# system.net
KiCad netlist of a schematic drawn in EAGLE
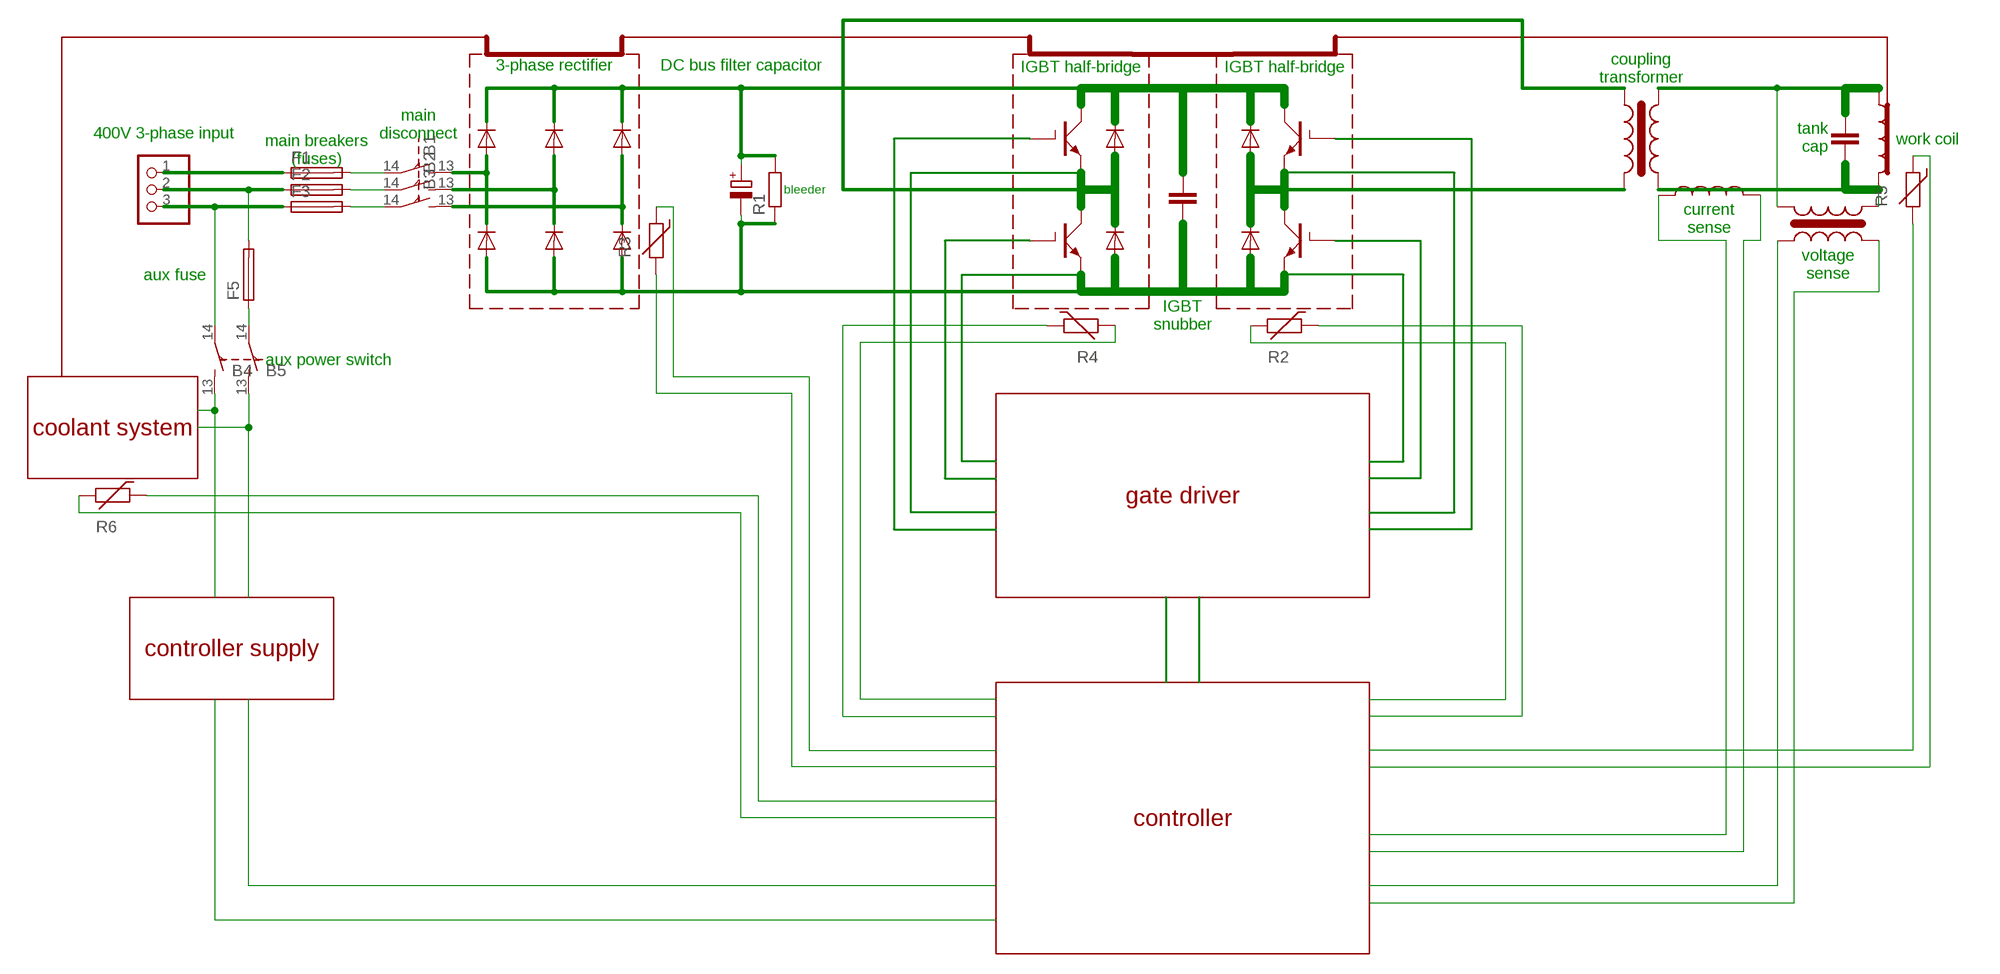
[diagram p0: schematic, sheet 1]

(export (version "E")
  (design (tool "Eeschema 10.0.6"))
  (components
    (comp (ref "B1")
      (value "ENDSCHALTER_SCHLIESSER")
      (footprint "eagle-import:ENDSCHALTER_SCHLIESSER")
      (libsource (lib "eagle-import") (part "ENDSCHALTER_SCHLIESSER"))
    )
    (comp (ref "B2")
      (value "ENDSCHALTER_SCHLIESSER")
      (footprint "eagle-import:ENDSCHALTER_SCHLIESSER")
      (libsource (lib "eagle-import") (part "ENDSCHALTER_SCHLIESSER"))
    )
    (comp (ref "B3")
      (value "ENDSCHALTER_SCHLIESSER")
      (footprint "eagle-import:ENDSCHALTER_SCHLIESSER")
      (libsource (lib "eagle-import") (part "ENDSCHALTER_SCHLIESSER"))
    )
    (comp (ref "B4")
      (value "ENDSCHALTER_SCHLIESSER")
      (footprint "eagle-import:ENDSCHALTER_SCHLIESSER")
      (libsource (lib "eagle-import") (part "ENDSCHALTER_SCHLIESSER"))
    )
    (comp (ref "B5")
      (value "ENDSCHALTER_SCHLIESSER")
      (footprint "eagle-import:ENDSCHALTER_SCHLIESSER")
      (libsource (lib "eagle-import") (part "ENDSCHALTER_SCHLIESSER"))
    )
    (comp (ref "C1")
      (value "CPOL-EU085CS-1AR")
      (footprint "eagle-import:085CS_1AR")
      (libsource (lib "eagle-import") (part "CPOL-EU085CS-1AR"))
    )
    (comp (ref "C2")
      (value "C-EU025-024X044")
      (footprint "eagle-import:C025-024X044")
      (libsource (lib "eagle-import") (part "C-EU025-024X044"))
    )
    (comp (ref "C3")
      (value "C-EU025-024X044")
      (footprint "eagle-import:C025-024X044")
      (libsource (lib "eagle-import") (part "C-EU025-024X044"))
    )
    (comp (ref "D1")
      (value "1N4004")
      (footprint "eagle-import:DO41-10")
      (libsource (lib "eagle-import") (part "1N4004"))
    )
    (comp (ref "D2")
      (value "1N4004")
      (footprint "eagle-import:DO41-10")
      (libsource (lib "eagle-import") (part "1N4004"))
    )
    (comp (ref "D3")
      (value "1N4004")
      (footprint "eagle-import:DO41-10")
      (libsource (lib "eagle-import") (part "1N4004"))
    )
    (comp (ref "D4")
      (value "1N4004")
      (footprint "eagle-import:DO41-10")
      (libsource (lib "eagle-import") (part "1N4004"))
    )
    (comp (ref "D5")
      (value "1N4004")
      (footprint "eagle-import:DO41-10")
      (libsource (lib "eagle-import") (part "1N4004"))
    )
    (comp (ref "D6")
      (value "1N4004")
      (footprint "eagle-import:DO41-10")
      (libsource (lib "eagle-import") (part "1N4004"))
    )
    (comp (ref "D7")
      (value "1N4004")
      (footprint "eagle-import:DO41-10")
      (libsource (lib "eagle-import") (part "1N4004"))
    )
    (comp (ref "D8")
      (value "1N4004")
      (footprint "eagle-import:DO41-10")
      (libsource (lib "eagle-import") (part "1N4004"))
    )
    (comp (ref "D9")
      (value "1N4004")
      (footprint "eagle-import:DO41-10")
      (libsource (lib "eagle-import") (part "1N4004"))
    )
    (comp (ref "D10")
      (value "1N4004")
      (footprint "eagle-import:DO41-10")
      (libsource (lib "eagle-import") (part "1N4004"))
    )
    (comp (ref "F1")
      (value "GSH15")
      (footprint "eagle-import:GSH15")
      (fields (field (name "MPN") "64900001039"))
      (libsource (lib "eagle-import") (part "GSH15"))
    )
    (comp (ref "F2")
      (value "GSH15")
      (footprint "eagle-import:GSH15")
      (fields (field (name "MPN") "64900001039"))
      (libsource (lib "eagle-import") (part "GSH15"))
    )
    (comp (ref "F3")
      (value "GSH15")
      (footprint "eagle-import:GSH15")
      (fields (field (name "MPN") "64900001039"))
      (libsource (lib "eagle-import") (part "GSH15"))
    )
    (comp (ref "F5")
      (value "GSH15")
      (footprint "eagle-import:GSH15")
      (fields (field (name "MPN") "64900001039"))
      (libsource (lib "eagle-import") (part "GSH15"))
    )
    (comp (ref "JP1")
      (value "PINHD-1X3")
      (footprint "eagle-import:1X03")
      (libsource (lib "eagle-import") (part "PINHD-1X3"))
    )
    (comp (ref "L1")
      (value "L-US0204/5")
      (footprint "eagle-import:0204_5")
      (libsource (lib "eagle-import") (part "L-US0204/5"))
    )
    (comp (ref "L12")
      (value "L-US0204/5")
      (footprint "eagle-import:0204_5")
      (libsource (lib "eagle-import") (part "L-US0204/5"))
    )
    (comp (ref "L13")
      (value "L-US0204/5")
      (footprint "eagle-import:0204_5")
      (libsource (lib "eagle-import") (part "L-US0204/5"))
    )
    (comp (ref "L14")
      (value "L-US0204/5")
      (footprint "eagle-import:0204_5")
      (libsource (lib "eagle-import") (part "L-US0204/5"))
    )
    (comp (ref "L15")
      (value "L-US0204/5")
      (footprint "eagle-import:0204_5")
      (libsource (lib "eagle-import") (part "L-US0204/5"))
    )
    (comp (ref "L16")
      (value "L-US0204/5")
      (footprint "eagle-import:0204_5")
      (libsource (lib "eagle-import") (part "L-US0204/5"))
    )
    (comp (ref "Q1")
      (value "IXGT6N170")
      (footprint "eagle-import:TO268")
      (libsource (lib "eagle-import") (part "IXG?N170T6"))
    )
    (comp (ref "Q2")
      (value "IXGT6N170")
      (footprint "eagle-import:TO268")
      (libsource (lib "eagle-import") (part "IXG?N170T6"))
    )
    (comp (ref "Q3")
      (value "IXGT6N170")
      (footprint "eagle-import:TO268")
      (libsource (lib "eagle-import") (part "IXG?N170T6"))
    )
    (comp (ref "Q4")
      (value "IXGT6N170")
      (footprint "eagle-import:TO268")
      (libsource (lib "eagle-import") (part "IXG?N170T6"))
    )
    (comp (ref "R1")
      (value "R-EU_0204/2V")
      (footprint "eagle-import:0204V")
      (libsource (lib "eagle-import") (part "R-EU_0204/2V"))
    )
    (comp (ref "R2")
      (value "THERMISTOR-2,5")
      (footprint "eagle-import:RS-2,5")
      (libsource (lib "eagle-import") (part "THERMISTOR-2,5"))
    )
    (comp (ref "R3")
      (value "THERMISTOR-2,5")
      (footprint "eagle-import:RS-2,5")
      (libsource (lib "eagle-import") (part "THERMISTOR-2,5"))
    )
    (comp (ref "R4")
      (value "THERMISTOR-2,5")
      (footprint "eagle-import:RS-2,5")
      (libsource (lib "eagle-import") (part "THERMISTOR-2,5"))
    )
    (comp (ref "R5")
      (value "THERMISTOR-2,5")
      (footprint "eagle-import:RS-2,5")
      (libsource (lib "eagle-import") (part "THERMISTOR-2,5"))
    )
    (comp (ref "R6")
      (value "THERMISTOR-2,5")
      (footprint "eagle-import:RS-2,5")
      (libsource (lib "eagle-import") (part "THERMISTOR-2,5"))
    )
  )
  (nets
    (net (code "1") (name "Net-(B1-3)") (class "Default")
      (node (ref "B1") (pin "13") (pinfunction "3_13") (pintype "passive"))
      (node (ref "D2") (pin "A") (pinfunction "A_A") (pintype "passive"))
      (node (ref "D3") (pin "C") (pinfunction "C_C") (pintype "passive"))
    )
    (net (code "2") (name "Net-(B1-4)") (class "Default")
      (node (ref "B1") (pin "14") (pinfunction "4_14") (pintype "passive"))
      (node (ref "F1") (pin "2") (pinfunction "2_2") (pintype "passive"))
    )
    (net (code "3") (name "Net-(B2-3)") (class "Default")
      (node (ref "B2") (pin "13") (pinfunction "3_13") (pintype "passive"))
      (node (ref "D4") (pin "A") (pinfunction "A_A") (pintype "passive"))
      (node (ref "D5") (pin "C") (pinfunction "C_C") (pintype "passive"))
    )
    (net (code "4") (name "Net-(B2-4)") (class "Default")
      (node (ref "B2") (pin "14") (pinfunction "4_14") (pintype "passive"))
      (node (ref "F2") (pin "2") (pinfunction "2_2") (pintype "passive"))
    )
    (net (code "5") (name "Net-(B3-3)") (class "Default")
      (node (ref "B3") (pin "13") (pinfunction "3_13") (pintype "passive"))
      (node (ref "D6") (pin "A") (pinfunction "A_A") (pintype "passive"))
      (node (ref "D7") (pin "C") (pinfunction "C_C") (pintype "passive"))
    )
    (net (code "6") (name "Net-(B3-4)") (class "Default")
      (node (ref "B3") (pin "14") (pinfunction "4_14") (pintype "passive"))
      (node (ref "F3") (pin "2") (pinfunction "2_2") (pintype "passive"))
    )
    (net (code "7") (name "Net-(B4-4)") (class "Default")
      (node (ref "B4") (pin "14") (pinfunction "4_14") (pintype "passive"))
      (node (ref "F3") (pin "1") (pinfunction "1_1") (pintype "passive"))
      (node (ref "JP1") (pin "3") (pinfunction "3_3") (pintype "passive"))
    )
    (net (code "8") (name "Net-(B5-4)") (class "Default")
      (node (ref "B5") (pin "14") (pinfunction "4_14") (pintype "passive"))
      (node (ref "F5") (pin "1") (pinfunction "1_1") (pintype "passive"))
    )
    (net (code "9") (name "Net-(C1-Pad+)") (class "Default")
      (node (ref "C1") (pin "+") (pinfunction "+_+") (pintype "passive"))
      (node (ref "C3") (pin "1") (pinfunction "1_1") (pintype "passive"))
      (node (ref "D10") (pin "C") (pinfunction "C_C") (pintype "passive"))
      (node (ref "D2") (pin "C") (pinfunction "C_C") (pintype "passive"))
      (node (ref "D4") (pin "C") (pinfunction "C_C") (pintype "passive"))
      (node (ref "D6") (pin "C") (pinfunction "C_C") (pintype "passive"))
      (node (ref "D8") (pin "C") (pinfunction "C_C") (pintype "passive"))
      (node (ref "Q2") (pin "C@1") (pinfunction "C_C@1") (pintype "passive"))
      (node (ref "Q2") (pin "C@2") (pinfunction "C_C@2") (pintype "passive"))
      (node (ref "Q4") (pin "C@1") (pinfunction "C_C@1") (pintype "passive"))
      (node (ref "Q4") (pin "C@2") (pinfunction "C_C@2") (pintype "passive"))
      (node (ref "R1") (pin "2") (pinfunction "2_2") (pintype "passive"))
    )
    (net (code "10") (name "Net-(C1-Pad-)") (class "Default")
      (node (ref "C1") (pin "-") (pinfunction "-_-") (pintype "passive"))
      (node (ref "C3") (pin "2") (pinfunction "2_2") (pintype "passive"))
      (node (ref "D1") (pin "A") (pinfunction "A_A") (pintype "passive"))
      (node (ref "D3") (pin "A") (pinfunction "A_A") (pintype "passive"))
      (node (ref "D5") (pin "A") (pinfunction "A_A") (pintype "passive"))
      (node (ref "D7") (pin "A") (pinfunction "A_A") (pintype "passive"))
      (node (ref "D9") (pin "A") (pinfunction "A_A") (pintype "passive"))
      (node (ref "Q1") (pin "E") (pinfunction "E_E") (pintype "passive"))
      (node (ref "Q3") (pin "E") (pinfunction "E_E") (pintype "passive"))
      (node (ref "R1") (pin "1") (pinfunction "1_1") (pintype "passive"))
    )
    (net (code "11") (name "Net-(C2-Pad1)") (class "Default")
      (node (ref "C2") (pin "1") (pinfunction "1_1") (pintype "passive"))
      (node (ref "L1") (pin "1") (pinfunction "1_1") (pintype "passive"))
      (node (ref "L14") (pin "1") (pinfunction "1_1") (pintype "passive"))
      (node (ref "L15") (pin "2") (pinfunction "2_2") (pintype "passive"))
    )
    (net (code "12") (name "Net-(C2-Pad2)") (class "Default")
      (node (ref "C2") (pin "2") (pinfunction "2_2") (pintype "passive"))
      (node (ref "L1") (pin "2") (pinfunction "2_2") (pintype "passive"))
      (node (ref "L14") (pin "2") (pinfunction "2_2") (pintype "passive"))
      (node (ref "L15") (pin "1") (pinfunction "1_1") (pintype "passive"))
    )
    (net (code "13") (name "Net-(D1-PadC)") (class "Default")
      (node (ref "D1") (pin "C") (pinfunction "C_C") (pintype "passive"))
      (node (ref "D8") (pin "A") (pinfunction "A_A") (pintype "passive"))
      (node (ref "L13") (pin "1") (pinfunction "1_1") (pintype "passive"))
      (node (ref "Q1") (pin "C@1") (pinfunction "C_C@1") (pintype "passive"))
      (node (ref "Q1") (pin "C@2") (pinfunction "C_C@2") (pintype "passive"))
      (node (ref "Q2") (pin "E") (pinfunction "E_E") (pintype "passive"))
    )
    (net (code "14") (name "Net-(D10-PadA)") (class "Default")
      (node (ref "D10") (pin "A") (pinfunction "A_A") (pintype "passive"))
      (node (ref "D9") (pin "C") (pinfunction "C_C") (pintype "passive"))
      (node (ref "L13") (pin "2") (pinfunction "2_2") (pintype "passive"))
      (node (ref "Q3") (pin "C@1") (pinfunction "C_C@1") (pintype "passive"))
      (node (ref "Q3") (pin "C@2") (pinfunction "C_C@2") (pintype "passive"))
      (node (ref "Q4") (pin "E") (pinfunction "E_E") (pintype "passive"))
    )
    (net (code "15") (name "Net-(F1-Pad1)") (class "Default")
      (node (ref "F1") (pin "1") (pinfunction "1_1") (pintype "passive"))
      (node (ref "JP1") (pin "1") (pinfunction "1_1") (pintype "passive"))
    )
    (net (code "16") (name "Net-(F2-Pad1)") (class "Default")
      (node (ref "F2") (pin "1") (pinfunction "1_1") (pintype "passive"))
      (node (ref "F5") (pin "2") (pinfunction "2_2") (pintype "passive"))
      (node (ref "JP1") (pin "2") (pinfunction "2_2") (pintype "passive"))
    )
    (net (code "17") (name "unconnected-(B4-3-Pad13)") (class "Default")
      (node (ref "B4") (pin "13") (pinfunction "3_13") (pintype "passive"))
    )
    (net (code "18") (name "unconnected-(B5-3-Pad13)") (class "Default")
      (node (ref "B5") (pin "13") (pinfunction "3_13") (pintype "passive"))
    )
    (net (code "19") (name "unconnected-(L12-Pad1)") (class "Default")
      (node (ref "L12") (pin "1") (pinfunction "1_1") (pintype "passive"))
    )
    (net (code "20") (name "unconnected-(L12-Pad2)") (class "Default")
      (node (ref "L12") (pin "2") (pinfunction "2_2") (pintype "passive"))
    )
    (net (code "21") (name "unconnected-(L16-Pad1)") (class "Default")
      (node (ref "L16") (pin "1") (pinfunction "1_1") (pintype "passive"))
    )
    (net (code "22") (name "unconnected-(L16-Pad2)") (class "Default")
      (node (ref "L16") (pin "2") (pinfunction "2_2") (pintype "passive"))
    )
    (net (code "23") (name "unconnected-(Q1-PadG)") (class "Default")
      (node (ref "Q1") (pin "G") (pinfunction "G_G") (pintype "passive"))
    )
    (net (code "24") (name "unconnected-(Q2-PadG)") (class "Default")
      (node (ref "Q2") (pin "G") (pinfunction "G_G") (pintype "passive"))
    )
    (net (code "25") (name "unconnected-(Q3-PadG)") (class "Default")
      (node (ref "Q3") (pin "G") (pinfunction "G_G") (pintype "passive"))
    )
    (net (code "26") (name "unconnected-(Q4-PadG)") (class "Default")
      (node (ref "Q4") (pin "G") (pinfunction "G_G") (pintype "passive"))
    )
    (net (code "27") (name "unconnected-(R2-Pad1)") (class "Default")
      (node (ref "R2") (pin "1") (pinfunction "1_1") (pintype "passive"))
    )
    (net (code "28") (name "unconnected-(R2-Pad2)") (class "Default")
      (node (ref "R2") (pin "2") (pinfunction "2_2") (pintype "passive"))
    )
    (net (code "29") (name "unconnected-(R3-Pad1)") (class "Default")
      (node (ref "R3") (pin "1") (pinfunction "1_1") (pintype "passive"))
    )
    (net (code "30") (name "unconnected-(R3-Pad2)") (class "Default")
      (node (ref "R3") (pin "2") (pinfunction "2_2") (pintype "passive"))
    )
    (net (code "31") (name "unconnected-(R4-Pad1)") (class "Default")
      (node (ref "R4") (pin "1") (pinfunction "1_1") (pintype "passive"))
    )
    (net (code "32") (name "unconnected-(R4-Pad2)") (class "Default")
      (node (ref "R4") (pin "2") (pinfunction "2_2") (pintype "passive"))
    )
    (net (code "33") (name "unconnected-(R5-Pad1)") (class "Default")
      (node (ref "R5") (pin "1") (pinfunction "1_1") (pintype "passive"))
    )
    (net (code "34") (name "unconnected-(R5-Pad2)") (class "Default")
      (node (ref "R5") (pin "2") (pinfunction "2_2") (pintype "passive"))
    )
    (net (code "35") (name "unconnected-(R6-Pad1)") (class "Default")
      (node (ref "R6") (pin "1") (pinfunction "1_1") (pintype "passive"))
    )
    (net (code "36") (name "unconnected-(R6-Pad2)") (class "Default")
      (node (ref "R6") (pin "2") (pinfunction "2_2") (pintype "passive"))
    )
  )
)
